# Sheet2.net
KiCad netlist of a schematic drawn in Altium Designer
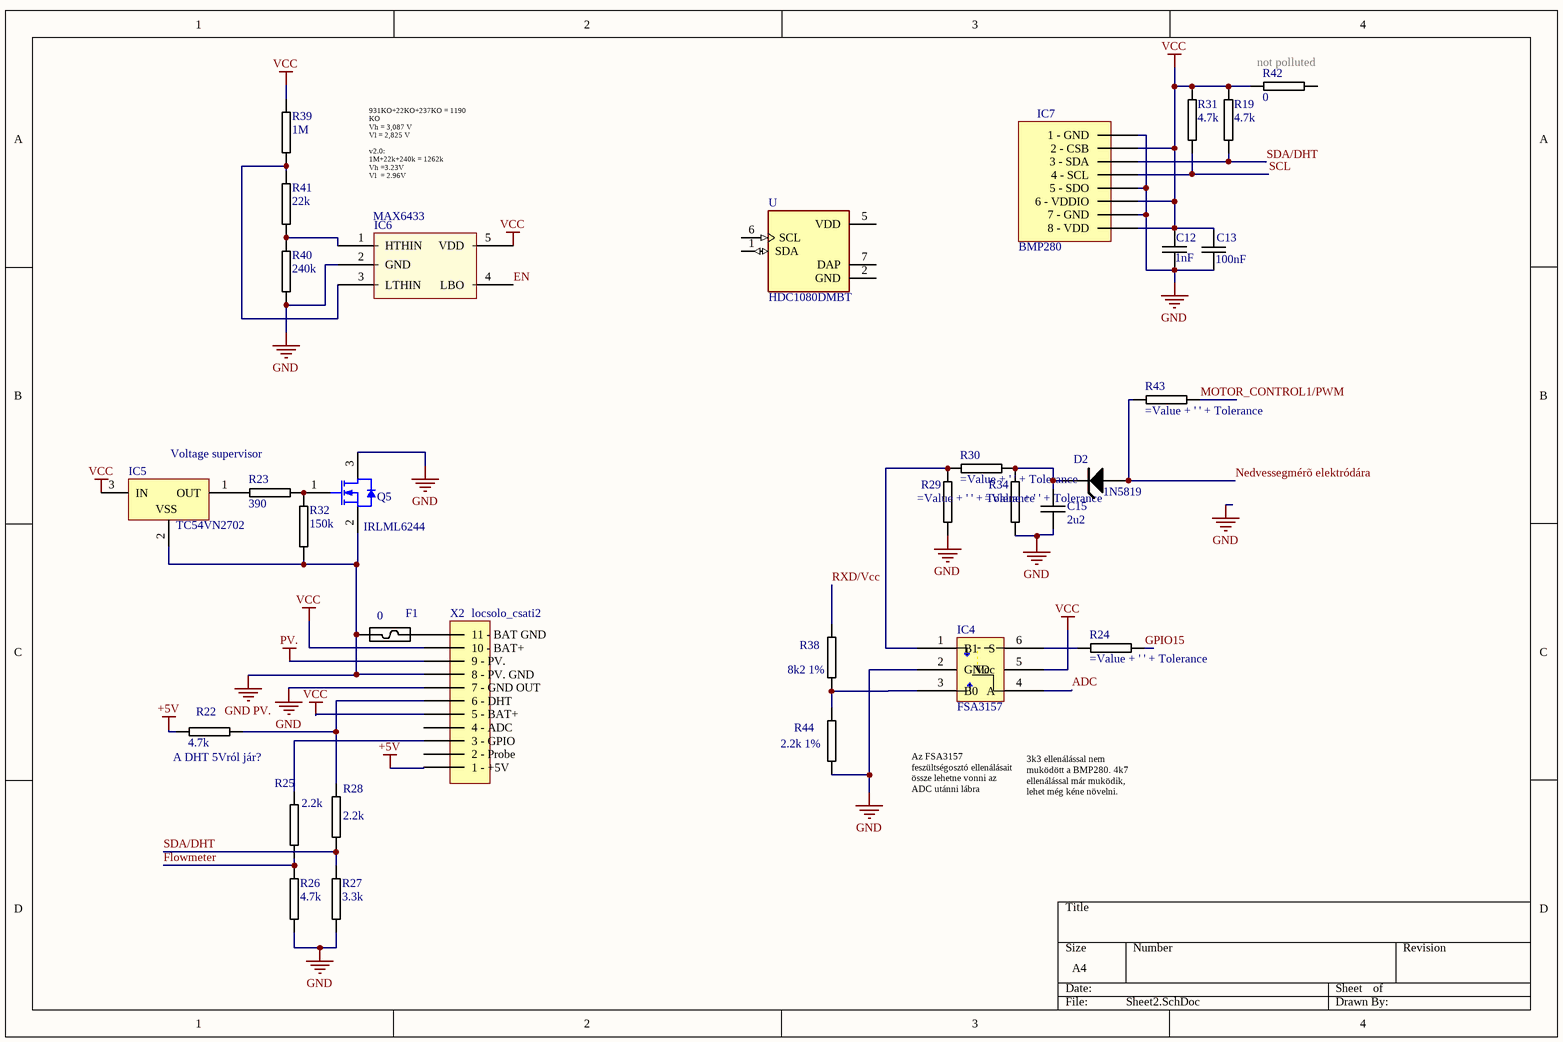
[diagram p0: Sheet2.SchDoc]

(export (version "E")
  (design (tool "Eeschema 10.0.6"))
  (components
    (comp (ref "C12")
      (value "1nF")
      (footprint "0805C-GENERIC")
      (description "100nF")
      (libsource (lib "vh_altium_library") (part "C0805-GENERIC"))
    )
    (comp (ref "C13")
      (value "100nF")
      (footprint "0805C-GENERIC")
      (libsource (lib "vh_altium_library") (part "C0805-GENERIC"))
    )
    (comp (ref "C15")
      (value "2u2")
      (footprint "0805C-GENERIC")
      (description "CAPACITOR 0805 CERAMIC")
      (fields
        (field (name "MANUFACTURER PART NUMBER") "ECJ-1VB0J225K")
        (field (name "MANUFACTURER") "Panasonic - ECG")
      )
      (libsource (lib "vh_altium_library") (part "0805C-2U2-6V3-X5R-PAN"))
    )
    (comp (ref "D2")
      (value "1N5819")
      (footprint "sod-123")
      (description "1N5819 SOD123")
      (libsource (lib "vh_altium_library") (part "BZT52C5V6"))
    )
    (comp (ref "F1") (value "0") (footprint "Fuse_1206") (libsource (lib "Fuse_1206") (part "Fuse")))
    (comp (ref "IC4") (value "FSA3157") (footprint "SC70-6") (libsource (lib "components") (part "FSA3157")))
    (comp (ref "IC5")
      (value "TC54VN2702")
      (footprint "SOT-23A-CB3_L")
      (fields (field (name "PUBLISHER") "Altium Limited"))
      (libsource (lib "Microchip Power Mgt Voltage Detector") (part "TC54VN2702ECB713"))
    )
    (comp (ref "IC6")
      (value "MAX6433")
      (footprint "SOT23-5")
      (description "MAX6433-MAX6435")
      (libsource (lib "components") (part "MAX6433-MAX6435"))
    )
    (comp (ref "IC7") (value "BMP280") (footprint "BMP280") (libsource (lib "components") (part "BMP280")))
    (comp (ref "Q5")
      (value "IRLML6244")
      (footprint "INF-PG-SOT23_N")
      (fields (field (name "MANUFACTURER") "Infineon") (field (name "PARTNUMBER") "BSS806N"))
      (libsource (lib "Infineon_Power_MOSFET") (part "BSS806N"))
    )
    (comp (ref "R19")
      (value "4.7k")
      (footprint "0805R-4K7")
      (description "RESISTOR 0805 1/4 WATT THIN FILM")
      (libsource (lib "vh_altium_library") (part "0805R-4K7"))
    )
    (comp (ref "R22")
      (value "4.7k")
      (footprint "0805R-4K7")
      (description "RESISTOR 0805 1/4 WATT THIN FILM")
      (libsource (lib "vh_altium_library") (part "0805R-4K7"))
    )
    (comp (ref "R23")
      (value "390")
      (footprint "0805R-470")
      (description "RESISTOR 0805 1/4 WATT THIN FILM")
      (libsource (lib "vh_altium_library") (part "0805R-470"))
    )
    (comp (ref "R24")
      (value "390")
      (footprint "0805R-390")
      (description "RESISTOR 0805 1/4 WATT THIN FILM")
      (libsource (lib "vh_altium_library") (part "0805R-390"))
    )
    (comp (ref "R25")
      (value "2.2k")
      (footprint "0805R-4K7")
      (description "RESISTOR 0805 1/4 WATT THIN FILM")
      (libsource (lib "vh_altium_library") (part "0805R-4K7"))
    )
    (comp (ref "R26")
      (value "4.7k")
      (footprint "0805R-4K7")
      (description "RESISTOR 0805 1/4 WATT THIN FILM")
      (libsource (lib "vh_altium_library") (part "0805R-4K7"))
    )
    (comp (ref "R27")
      (value "3.3k")
      (footprint "0805R-4K7")
      (description "RESISTOR 0805 1/4 WATT THIN FILM")
      (libsource (lib "vh_altium_library") (part "0805R-4K7"))
    )
    (comp (ref "R28")
      (value "2.2k")
      (footprint "0805R-4K7")
      (description "RESISTOR 0805 1/4 WATT THIN FILM")
      (libsource (lib "vh_altium_library") (part "0805R-4K7"))
    )
    (comp (ref "R29")
      (value "100k")
      (footprint "0805R-100")
      (description "RESISTOR 0805 1/4 WATT THIN FILM")
      (libsource (lib "vh_altium_library") (part "0805R-100"))
    )
    (comp (ref "R30")
      (value "220k")
      (footprint "0805R-100")
      (description "RESISTOR 0805 1/4 WATT THIN FILM")
      (libsource (lib "vh_altium_library") (part "0805R-100"))
    )
    (comp (ref "R31")
      (value "4.7k")
      (footprint "0805R-4K7")
      (description "RESISTOR 0805 1/4 WATT THIN FILM")
      (libsource (lib "vh_altium_library") (part "0805R-4K7"))
    )
    (comp (ref "R32")
      (value "150k")
      (footprint "0805R-150K")
      (description "RESISTOR 0805 1/4 WATT THIN FILM")
      (libsource (lib "vh_altium_library") (part "0805R-150K"))
    )
    (comp (ref "R34")
      (value "510k")
      (footprint "0805R-100")
      (description "RESISTOR 0805 1/4 WATT THIN FILM")
      (libsource (lib "vh_altium_library") (part "0805R-100"))
    )
    (comp (ref "R38")
      (value "8k2 1%")
      (footprint "0805R-4K7")
      (description "RESISTOR 0805 1/4 WATT THIN FILM")
      (fields (field (name "TOLERANCE") "1%"))
      (libsource (lib "vh_altium_library") (part "0805R-4K7"))
    )
    (comp (ref "R39")
      (value "1M")
      (footprint "0805R-TBD")
      (description "RESISTOR 0805 VALUE TO BE DETERMINED")
      (libsource (lib "vh_altium_library") (part "0805R-TBD"))
    )
    (comp (ref "R40")
      (value "240k")
      (footprint "0805R-TBD")
      (description "RESISTOR 0805 VALUE TO BE DETERMINED")
      (libsource (lib "vh_altium_library") (part "0805R-TBD"))
    )
    (comp (ref "R41")
      (value "22k")
      (footprint "0805R-TBD")
      (description "RESISTOR 0805 VALUE TO BE DETERMINED")
      (libsource (lib "vh_altium_library") (part "0805R-TBD"))
    )
    (comp (ref "R42")
      (value "0")
      (footprint "0805R-TBD")
      (description "RESISTOR 0805 VALUE TO BE DETERMINED")
      (libsource (lib "vh_altium_library") (part "0805R-TBD"))
    )
    (comp (ref "R43")
      (value "100k")
      (footprint "0805R-100")
      (description "RESISTOR 0805 1/4 WATT THIN FILM")
      (libsource (lib "vh_altium_library") (part "0805R-100"))
    )
    (comp (ref "R44")
      (value "2.2k 1%")
      (footprint "0805R-1K")
      (description "RESISTOR 0805 1/4 WATT THIN FILM")
      (fields (field (name "TOLERANCE") "1%"))
      (libsource (lib "vh_altium_library") (part "0805R-1K"))
    )
    (comp (ref "U")
      (value "HDC1080DMBT")
      (footprint "SON100P300X300X80-7N")
      (description "Humidity Temperature Sensor 0 ~ 100% RH IÂ²C Â±2% RH 15s Surface Mount")
      (fields (field (name "MF") "Texas Instruments"))
      (libsource (lib "WateringSystem_Library") (part "HDC1080DMBT"))
    )
    (comp (ref "X2")
      (value "locsolo_csati2")
      (footprint "locsolo_csati2")
      (libsource (lib "components") (part "locsolo_csati2"))
    )
  )
  (nets
    (net (code "1") (name "+5V") (class "Default")
      (node (ref "R22") (pin "1") (pintype "passive"))
      (node (ref "X2") (pin "1") (pinfunction "1_-_+5V_1") (pintype "passive"))
    )
    (net (code "2") (name "/ADC") (class "Default")
      (node (ref "IC4") (pin "4") (pinfunction "A_4") (pintype "passive"))
    )
    (net (code "3") (name "/EN") (class "Default")
      (node (ref "IC6") (pin "4") (pinfunction "LBO_4") (pintype "passive"))
    )
    (net (code "4") (name "/Flowmeter") (class "Default")
      (node (ref "R25") (pin "1") (pintype "passive"))
      (node (ref "R26") (pin "2") (pintype "passive"))
    )
    (net (code "5") (name "/GPIO15") (class "Default") (node (ref "R24") (pin "1") (pintype "passive")))
    (net (code "6") (name "/MOTOR_CONTROL1{slash}PWM") (class "Default")
      (node (ref "R43") (pin "1") (pintype "passive"))
    )
    (net (code "7") (name "/Nedvessegmérõ elektródára") (class "Default")
      (node (ref "D2") (pin "A") (pinfunction "A_A") (pintype "passive"))
      (node (ref "R43") (pin "2") (pintype "passive"))
    )
    (net (code "8") (name "/RXD{slash}Vcc") (class "Default")
      (node (ref "R38") (pin "1") (pintype "passive"))
    )
    (net (code "9") (name "/SCL") (class "Default")
      (node (ref "IC7") (pin "4") (pinfunction "4_-_SCL_4") (pintype "passive"))
      (node (ref "R31") (pin "1") (pintype "passive"))
    )
    (net (code "10") (name "/SDA{slash}DHT") (class "Default")
      (node (ref "IC7") (pin "3") (pinfunction "3_-_SDA_3") (pintype "passive"))
      (node (ref "R19") (pin "1") (pintype "passive"))
      (node (ref "R27") (pin "2") (pintype "passive"))
      (node (ref "R28") (pin "1") (pintype "passive"))
    )
    (net (code "11") (name "GND") (class "Default")
      (node (ref "C12") (pin "2") (pintype "passive"))
      (node (ref "C13") (pin "2") (pintype "passive"))
      (node (ref "C15") (pin "2") (pintype "passive"))
      (node (ref "IC4") (pin "2") (pinfunction "GND_2") (pintype "passive"))
      (node (ref "IC6") (pin "2") (pinfunction "GND_2") (pintype "passive"))
      (node (ref "IC7") (pin "1") (pinfunction "1_-_GND_1") (pintype "passive"))
      (node (ref "IC7") (pin "5") (pinfunction "5_-_SDO_5") (pintype "passive"))
      (node (ref "IC7") (pin "7") (pinfunction "7_-_GND_7") (pintype "passive"))
      (node (ref "Q5") (pin "3") (pinfunction "DRAIN_3") (pintype "passive"))
      (node (ref "R26") (pin "1") (pintype "passive"))
      (node (ref "R27") (pin "1") (pintype "passive"))
      (node (ref "R29") (pin "1") (pintype "passive"))
      (node (ref "R34") (pin "1") (pintype "passive"))
      (node (ref "R40") (pin "2") (pintype "passive"))
      (node (ref "R44") (pin "1") (pintype "passive"))
      (node (ref "X2") (pin "7") (pinfunction "7_-_GND_OUT_7") (pintype "passive"))
    )
    (net (code "12") (name "GND PV.") (class "Default")
      (node (ref "F1") (pin "1") (pintype "passive"))
      (node (ref "IC5") (pin "2") (pinfunction "VSS_2") (pintype "power_in"))
      (node (ref "Q5") (pin "2") (pinfunction "SOURCE_2") (pintype "passive"))
      (node (ref "R32") (pin "2") (pintype "passive"))
      (node (ref "X2") (pin "8") (pinfunction "8_-_PV._GND_8") (pintype "passive"))
    )
    (net (code "13") (name "Net-(C15-Pad1)") (class "Default")
      (node (ref "C15") (pin "1") (pintype "passive"))
      (node (ref "D2") (pin "K") (pinfunction "K_K") (pintype "passive"))
      (node (ref "R30") (pin "1") (pintype "passive"))
      (node (ref "R34") (pin "2") (pintype "passive"))
    )
    (net (code "14") (name "Net-(IC4-B0)") (class "Default")
      (node (ref "IC4") (pin "3") (pinfunction "B0_3") (pintype "passive"))
      (node (ref "R38") (pin "2") (pintype "passive"))
      (node (ref "R44") (pin "2") (pintype "passive"))
    )
    (net (code "15") (name "Net-(IC4-B1)") (class "Default")
      (node (ref "IC4") (pin "1") (pinfunction "B1_1") (pintype "passive"))
      (node (ref "R29") (pin "2") (pintype "passive"))
      (node (ref "R30") (pin "2") (pintype "passive"))
    )
    (net (code "16") (name "Net-(IC4-S)") (class "Default")
      (node (ref "IC4") (pin "6") (pinfunction "S_6") (pintype "passive"))
      (node (ref "R24") (pin "2") (pintype "passive"))
    )
    (net (code "17") (name "Net-(IC5-OUT)") (class "Default")
      (node (ref "IC5") (pin "1") (pinfunction "OUT_1") (pintype "power_in"))
      (node (ref "R23") (pin "1") (pintype "passive"))
    )
    (net (code "18") (name "Net-(IC6-HTHIN)") (class "Default")
      (node (ref "IC6") (pin "1") (pinfunction "HTHIN_1") (pintype "passive"))
      (node (ref "R40") (pin "1") (pintype "passive"))
      (node (ref "R41") (pin "2") (pintype "passive"))
    )
    (net (code "19") (name "Net-(IC6-LTHIN)") (class "Default")
      (node (ref "IC6") (pin "3") (pinfunction "LTHIN_3") (pintype "passive"))
      (node (ref "R39") (pin "1") (pintype "passive"))
      (node (ref "R41") (pin "1") (pintype "passive"))
    )
    (net (code "20") (name "Net-(Q5-GATE)") (class "Default")
      (node (ref "Q5") (pin "1") (pinfunction "GATE_1") (pintype "passive"))
      (node (ref "R23") (pin "2") (pintype "passive"))
      (node (ref "R32") (pin "1") (pintype "passive"))
    )
    (net (code "21") (name "Net-(X2-3_-_GPIO)") (class "Default")
      (node (ref "R25") (pin "2") (pintype "passive"))
      (node (ref "X2") (pin "3") (pinfunction "3_-_GPIO_3") (pintype "passive"))
    )
    (net (code "22") (name "Net-(X2-6_-_DHT)") (class "Default")
      (node (ref "R22") (pin "2") (pintype "passive"))
      (node (ref "R28") (pin "2") (pintype "passive"))
      (node (ref "X2") (pin "6") (pinfunction "6_-_DHT_6") (pintype "passive"))
    )
    (net (code "23") (name "Net-(X2-11_-_BAT_GND)") (class "Default")
      (node (ref "F1") (pin "2") (pintype "passive"))
      (node (ref "X2") (pin "11") (pinfunction "11_-_BAT_GND_11") (pintype "passive"))
    )
    (net (code "24") (name "PV.") (class "Default")
      (node (ref "X2") (pin "9") (pinfunction "9_-_PV._9") (pintype "passive"))
    )
    (net (code "25") (name "VCC") (class "Default")
      (node (ref "C12") (pin "1") (pintype "passive"))
      (node (ref "C13") (pin "1") (pintype "passive"))
      (node (ref "IC4") (pin "5") (pinfunction "Vcc_5") (pintype "passive"))
      (node (ref "IC5") (pin "3") (pinfunction "IN_3") (pintype "power_in"))
      (node (ref "IC6") (pin "5") (pinfunction "VDD_5") (pintype "passive"))
      (node (ref "IC7") (pin "2") (pinfunction "2_-_CSB_2") (pintype "passive"))
      (node (ref "IC7") (pin "6") (pinfunction "6_-_VDDIO_6") (pintype "passive"))
      (node (ref "IC7") (pin "8") (pinfunction "8_-_VDD_8") (pintype "passive"))
      (node (ref "R19") (pin "2") (pintype "passive"))
      (node (ref "R31") (pin "2") (pintype "passive"))
      (node (ref "R39") (pin "2") (pintype "passive"))
      (node (ref "R42") (pin "1") (pintype "passive"))
      (node (ref "X2") (pin "10") (pinfunction "10_-_BAT+_10") (pintype "passive"))
      (node (ref "X2") (pin "5") (pinfunction "5_-_BAT+_5") (pintype "passive"))
    )
    (net (code "26") (name "unconnected-(R42-Pad2)") (class "Default")
      (node (ref "R42") (pin "2") (pintype "passive"))
    )
    (net (code "27") (name "unconnected-(U-DAP-Pad7)") (class "Default")
      (node (ref "U") (pin "7") (pinfunction "DAP_7") (pintype "power_in"))
    )
    (net (code "28") (name "unconnected-(U-GND-Pad2)") (class "Default")
      (node (ref "U") (pin "2") (pinfunction "GND_2") (pintype "power_in"))
    )
    (net (code "29") (name "unconnected-(U-SCL-Pad6)") (class "Default")
      (node (ref "U") (pin "6") (pinfunction "SCL_6") (pintype "input"))
    )
    (net (code "30") (name "unconnected-(U-SDA-Pad1)") (class "Default")
      (node (ref "U") (pin "1") (pinfunction "SDA_1") (pintype "bidirectional"))
    )
    (net (code "31") (name "unconnected-(U-VDD-Pad5)") (class "Default")
      (node (ref "U") (pin "5") (pinfunction "VDD_5") (pintype "power_in"))
    )
    (net (code "32") (name "unconnected-(X2-2_-_Probe-Pad2)") (class "Default")
      (node (ref "X2") (pin "2") (pinfunction "2_-_Probe_2") (pintype "passive"))
    )
    (net (code "33") (name "unconnected-(X2-4_-_ADC-Pad4)") (class "Default")
      (node (ref "X2") (pin "4") (pinfunction "4_-_ADC_4") (pintype "passive"))
    )
  )
)
